# Sheet1.net
KiCad netlist of a schematic drawn in Altium Designer
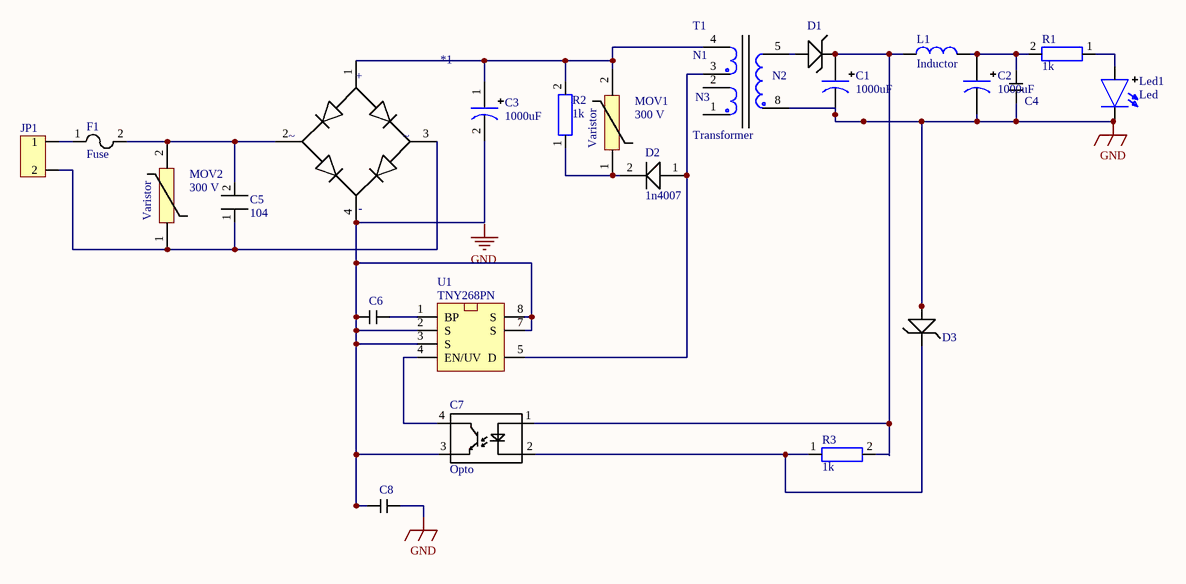
[diagram p0: Sheet1.SchDoc]

(export (version "E")
  (design (tool "Eeschema 10.0.6"))
  (components
    (comp (ref "*1")
      (value "Bridge diode")
      (footprint "bridge diode - duplicate")
      (libsource (lib "mylib") (part "Bridge diode"))
    )
    (comp (ref "C1")
      (value "1000uF")
      (footprint "Capacitor 1000uF 25V")
      (description "Capacitor Pol")
      (libsource (lib "mylib") (part "Capacitor Pol"))
    )
    (comp (ref "C2")
      (value "1000uF")
      (footprint "Capacitor 1000uF 25V")
      (description "Capacitor Pol")
      (libsource (lib "mylib") (part "Capacitor Pol"))
    )
    (comp (ref "C3")
      (value "1000uF")
      (footprint "Capacitor 1000uF 25V")
      (description "Capacitor Pol")
      (libsource (lib "") (part "Capacitor Pol_1"))
    )
    (comp (ref "C4") (value "104") (footprint "Capacitor 104") (libsource (lib "") (part "Capactor_1")))
    (comp (ref "C5") (value "104") (footprint "Capactor cbb") (libsource (lib "mylib") (part "Capactor")))
    (comp (ref "C6") (value "104") (footprint "Capacitor 104") (libsource (lib "") (part "Capactor_1")))
    (comp (ref "C7")
      (value "Opto")
      (footprint "Opto")
      (description "PC817")
      (libsource (lib "mylib") (part "Opto"))
    )
    (comp (ref "C8") (value "104") (footprint "Capactor cbb") (libsource (lib "") (part "Capactor_1")))
    (comp (ref "D1")
      (value "Diode zenner")
      (footprint "Diode Zenner")
      (libsource (lib "mylib") (part "Diode zenner"))
    )
    (comp (ref "D2")
      (value "1n4007")
      (footprint "Diode 1N4007")
      (description "diode 1n4007")
      (libsource (lib "mylib") (part "Diode"))
    )
    (comp (ref "D3")
      (value "Diode zenner")
      (footprint "Diode Zenner")
      (libsource (lib "mylib") (part "Diode zenner"))
    )
    (comp (ref "F1") (value "Fuse") (footprint "Fuse") (libsource (lib "mylib") (part "Fuse")))
    (comp (ref "JP1")
      (value "Header kf128")
      (footprint "Terminal 2")
      (description "Header kf128 banlinhkien")
      (libsource (lib "mylib") (part "Header kf128"))
    )
    (comp (ref "L1")
      (value "Inductor")
      (footprint "RLB 0712 Inductor")
      (libsource (lib "mylib") (part "Inductor"))
    )
    (comp (ref "Led1")
      (value "Led")
      (footprint "LED RED")
      (description "Led Red")
      (libsource (lib "mylib") (part "Led"))
    )
    (comp (ref "MOV1")
      (value "300 V")
      (footprint "Varistor 10d471k")
      (description "Varistor mov 10d471k   12 - 300 V")
      (libsource (lib "mylib") (part "Varistor 10d471k"))
    )
    (comp (ref "MOV2")
      (value "300 V")
      (footprint "Varistor 10d471k")
      (description "Varistor mov 10d471k   12 - 300 V")
      (libsource (lib "mylib") (part "Varistor 10d471k"))
    )
    (comp (ref "R1")
      (value "1k")
      (footprint "Resistor 1/4w")
      (description "Resister")
      (libsource (lib "") (part "Resister_1"))
    )
    (comp (ref "R2")
      (value "1k")
      (footprint "Resistor 1/4w - duplicate")
      (description "Resister")
      (libsource (lib "mylib") (part "Resister"))
    )
    (comp (ref "R3")
      (value "1k")
      (footprint "Resistor 1/4w - duplicate")
      (description "Resister")
      (libsource (lib "") (part "Resister_2"))
    )
    (comp (ref "T1")
      (value "Transformer")
      (footprint "Transformer")
      (description "BAX EE10-Q7LK6 pin")
      (libsource (lib "mylib") (part "Transformer"))
    )
    (comp (ref "U1") (value "TNY268PN") (footprint "TNY268pn") (libsource (lib "mylib") (part "TNY268PN")))
  )
  (nets
    (net (code "1") (name "GND") (class "Default")
      (node (ref "C1") (pin "2") (pinfunction "2_2") (pintype "passive"))
      (node (ref "C2") (pin "2") (pinfunction "2_2") (pintype "passive"))
      (node (ref "C4") (pin "1") (pinfunction "1_1") (pintype "passive"))
      (node (ref "C8") (pin "2") (pinfunction "2_2") (pintype "passive"))
      (node (ref "D3") (pin "1") (pinfunction "1_1") (pintype "passive"))
      (node (ref "Led1") (pin "2") (pinfunction "2_2") (pintype "passive"))
      (node (ref "T1") (pin "8") (pinfunction "8_8") (pintype "passive"))
    )
    (net (code "2") (name "Net-(*1-Pad1)") (class "Default")
      (node (ref "*1") (pin "1") (pinfunction "1_1") (pintype "passive"))
      (node (ref "C3") (pin "1") (pinfunction "1_1") (pintype "passive"))
      (node (ref "MOV1") (pin "2") (pinfunction "2_2") (pintype "passive"))
      (node (ref "R2") (pin "2") (pinfunction "2_2") (pintype "passive"))
      (node (ref "T1") (pin "4") (pinfunction "4_4") (pintype "passive"))
    )
    (net (code "3") (name "Net-(*1-Pad2)") (class "Default")
      (node (ref "*1") (pin "2") (pinfunction "2_2") (pintype "passive"))
      (node (ref "C5") (pin "2") (pinfunction "2_2") (pintype "passive"))
      (node (ref "F1") (pin "2") (pinfunction "2_2") (pintype "passive"))
      (node (ref "MOV2") (pin "2") (pinfunction "2_2") (pintype "passive"))
    )
    (net (code "4") (name "Net-(*1-Pad3)") (class "Default")
      (node (ref "*1") (pin "3") (pinfunction "3_3") (pintype "passive"))
      (node (ref "C5") (pin "1") (pinfunction "1_1") (pintype "passive"))
      (node (ref "JP1") (pin "2") (pinfunction "2_2") (pintype "passive"))
      (node (ref "MOV2") (pin "1") (pinfunction "1_1") (pintype "passive"))
    )
    (net (code "5") (name "Net-(*1-Pad4)") (class "Default")
      (node (ref "*1") (pin "4") (pinfunction "4_4") (pintype "passive"))
      (node (ref "C3") (pin "2") (pinfunction "2_2") (pintype "passive"))
      (node (ref "C6") (pin "1") (pinfunction "1_1") (pintype "passive"))
      (node (ref "C7") (pin "3") (pinfunction "3_3") (pintype "passive"))
      (node (ref "C8") (pin "1") (pinfunction "1_1") (pintype "passive"))
      (node (ref "U1") (pin "2") (pinfunction "S_2") (pintype "passive"))
      (node (ref "U1") (pin "3") (pinfunction "S_3") (pintype "passive"))
      (node (ref "U1") (pin "7") (pinfunction "S_7") (pintype "passive"))
      (node (ref "U1") (pin "8") (pinfunction "S_8") (pintype "passive"))
    )
    (net (code "6") (name "Net-(C1-Pad1)") (class "Default")
      (node (ref "C1") (pin "1") (pinfunction "1_1") (pintype "passive"))
      (node (ref "C7") (pin "1") (pinfunction "1_1") (pintype "passive"))
      (node (ref "D1") (pin "2") (pinfunction "2_2") (pintype "passive"))
      (node (ref "L1") (pin "1") (pinfunction "1_1") (pintype "passive"))
    )
    (net (code "7") (name "Net-(C2-Pad1)") (class "Default")
      (node (ref "C2") (pin "1") (pinfunction "1_1") (pintype "passive"))
      (node (ref "C4") (pin "2") (pinfunction "2_2") (pintype "passive"))
      (node (ref "L1") (pin "2") (pinfunction "2_2") (pintype "passive"))
      (node (ref "R1") (pin "2") (pinfunction "2_2") (pintype "passive"))
    )
    (net (code "8") (name "Net-(C7-Pad2)") (class "Default")
      (node (ref "C7") (pin "2") (pinfunction "2_2") (pintype "passive"))
      (node (ref "D3") (pin "2") (pinfunction "2_2") (pintype "passive"))
      (node (ref "R3") (pin "1") (pinfunction "1_1") (pintype "passive"))
    )
    (net (code "9") (name "Net-(D1-Pad1)") (class "Default")
      (node (ref "D1") (pin "1") (pinfunction "1_1") (pintype "passive"))
      (node (ref "T1") (pin "5") (pinfunction "5_5") (pintype "passive"))
    )
    (net (code "10") (name "Net-(D2-Pad2)") (class "Default")
      (node (ref "D2") (pin "2") (pinfunction "2_2") (pintype "passive"))
      (node (ref "MOV1") (pin "1") (pinfunction "1_1") (pintype "passive"))
      (node (ref "R2") (pin "1") (pinfunction "1_1") (pintype "passive"))
    )
    (net (code "11") (name "Net-(F1-Pad1)") (class "Default")
      (node (ref "F1") (pin "1") (pinfunction "1_1") (pintype "passive"))
      (node (ref "JP1") (pin "1") (pinfunction "1_1") (pintype "passive"))
    )
    (net (code "12") (name "Net-(Led1-Pad1)") (class "Default")
      (node (ref "Led1") (pin "1") (pinfunction "1_1") (pintype "passive"))
      (node (ref "R1") (pin "1") (pinfunction "1_1") (pintype "passive"))
    )
    (net (code "13") (name "Net-(U1-BP)") (class "Default")
      (node (ref "C6") (pin "2") (pinfunction "2_2") (pintype "passive"))
      (node (ref "U1") (pin "1") (pinfunction "BP_1") (pintype "passive"))
    )
    (net (code "14") (name "Net-(U1-D)") (class "Default")
      (node (ref "D2") (pin "1") (pinfunction "1_1") (pintype "passive"))
      (node (ref "T1") (pin "3") (pinfunction "3_3") (pintype "passive"))
      (node (ref "U1") (pin "5") (pinfunction "D_5") (pintype "passive"))
    )
    (net (code "15") (name "Net-(U1-EN{slash}UV)") (class "Default")
      (node (ref "C7") (pin "4") (pinfunction "4_4") (pintype "passive"))
      (node (ref "U1") (pin "4") (pinfunction "EN/UV_4") (pintype "passive"))
    )
    (net (code "16") (name "unconnected-(R3-Pad2)") (class "Default")
      (node (ref "R3") (pin "2") (pinfunction "2_2") (pintype "passive"))
    )
    (net (code "17") (name "unconnected-(T1-Pad1)") (class "Default")
      (node (ref "T1") (pin "1") (pinfunction "1_1") (pintype "passive"))
    )
    (net (code "18") (name "unconnected-(T1-Pad2)") (class "Default")
      (node (ref "T1") (pin "2") (pinfunction "2_2") (pintype "passive"))
    )
  )
)
